# main.net
KiCad netlist of a schematic drawn in EAGLE
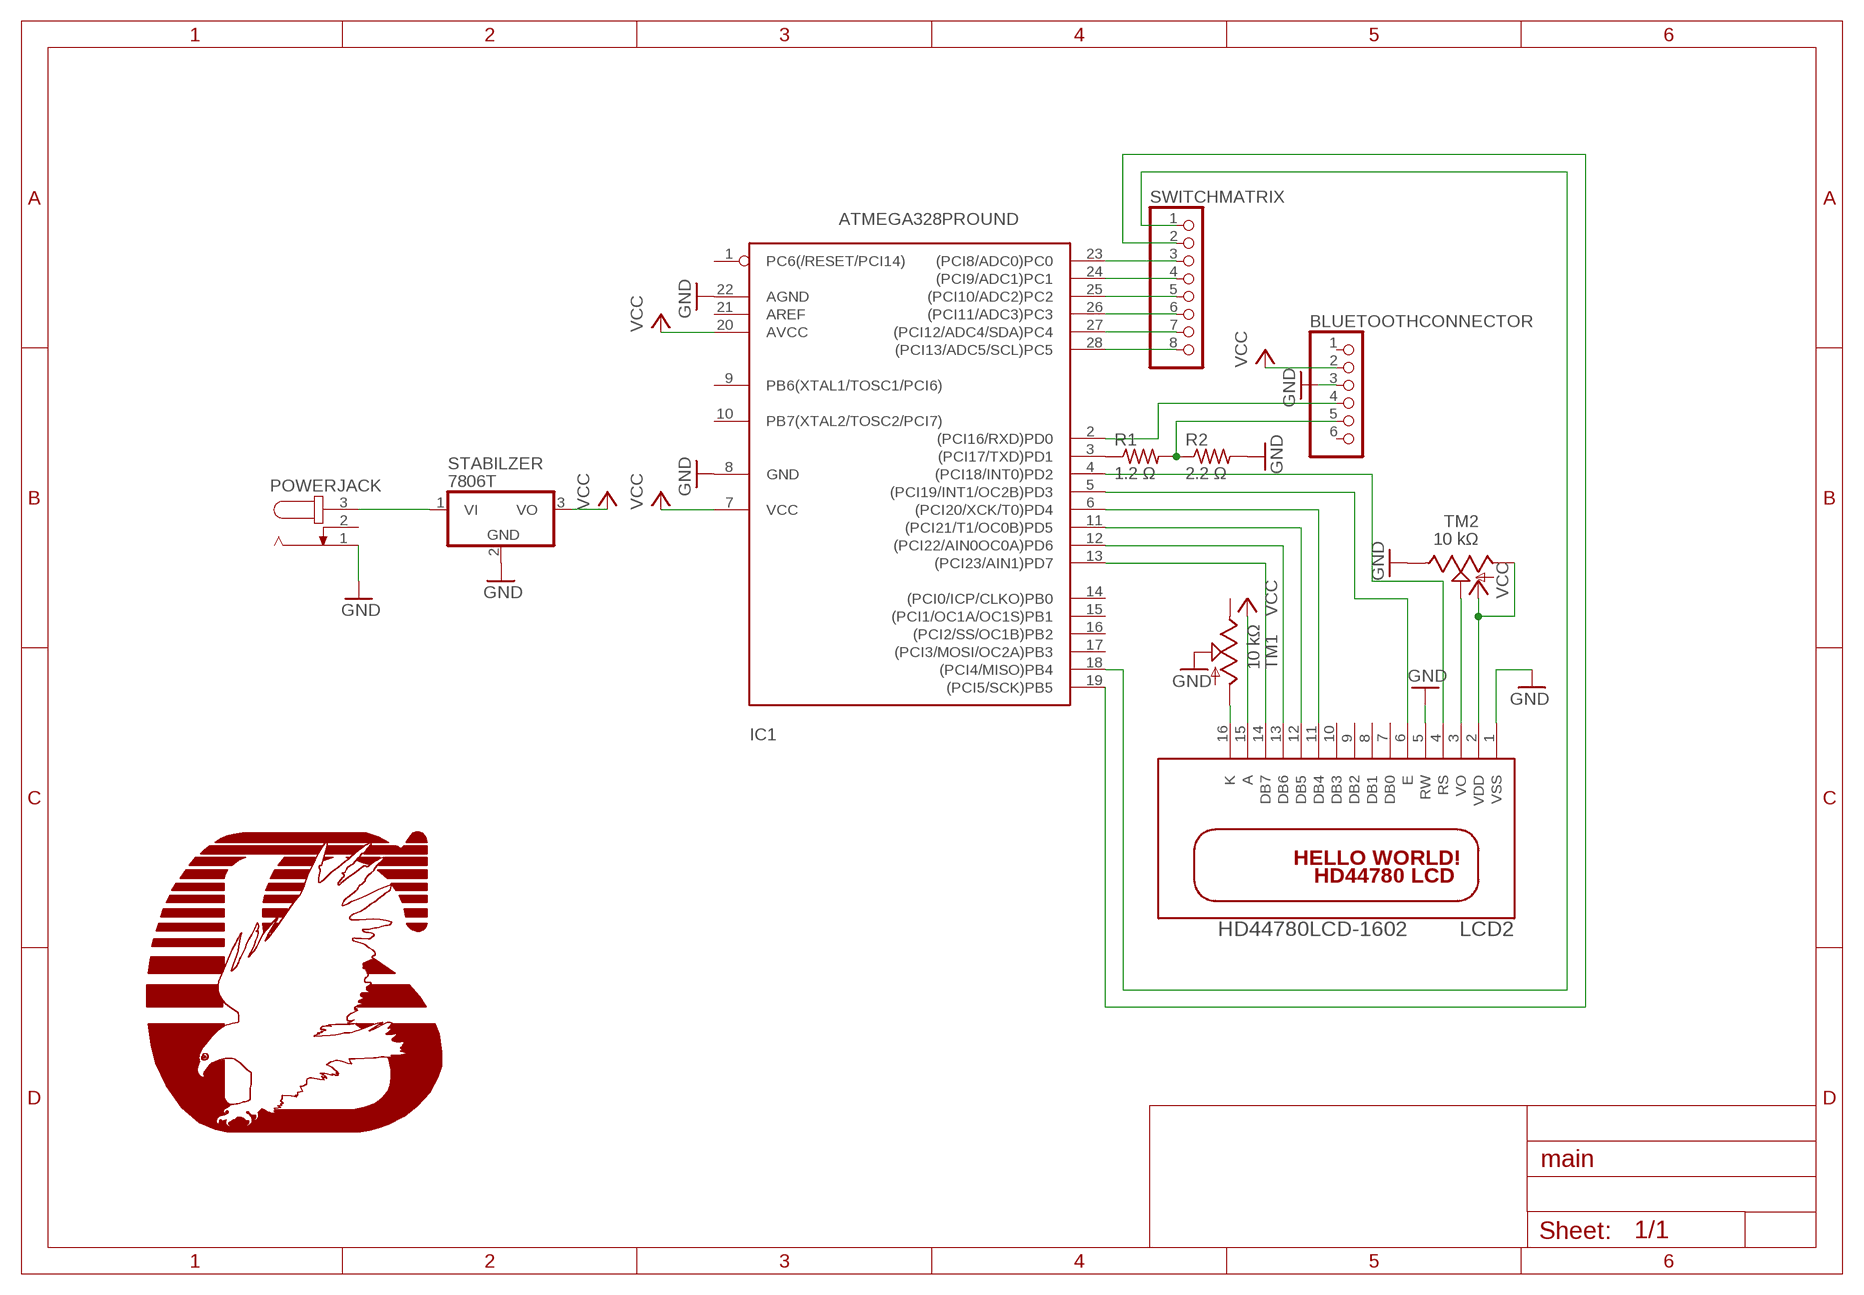
[diagram p0: schematic, sheet 1]

(export (version "E")
  (design (tool "Eeschema 10.0.6"))
  (components
    (comp (ref "BLUETOOTHCONNECTOR")
      (value "PINHD-1X6B")
      (footprint "eagle-import:1X06-BIG")
      (libsource (lib "eagle-import") (part "PINHD-1X6B"))
    )
    (comp (ref "IC1")
      (value "ATMEGA328PROUND")
      (footprint "eagle-import:DIL28-3-ROUND")
      (libsource (lib "eagle-import") (part "ATMEGA328PROUND"))
    )
    (comp (ref "LCD2")
      (value "HD44780LCD-1602")
      (footprint "eagle-import:LCD1602")
      (libsource (lib "eagle-import") (part "HD44780LCD-1602"))
    )
    (comp (ref "POWERJACK")
      (value "JACK-PLUG0")
      (footprint "eagle-import:SPC4077")
      (libsource (lib "eagle-import") (part "JACK-PLUG0"))
    )
    (comp (ref "R1")
      (value "1.2 Ω")
      (footprint "eagle-import:0207_10")
      (libsource (lib "eagle-import") (part "R-US_0207/10"))
    )
    (comp (ref "R2")
      (value "2.2 Ω")
      (footprint "eagle-import:0207_10")
      (libsource (lib "eagle-import") (part "R-US_0207/10"))
    )
    (comp (ref "STABILZER")
      (value "7806T")
      (footprint "eagle-import:TO220H")
      (libsource (lib "eagle-import") (part "78T06"))
    )
    (comp (ref "SWITCHMATRIX")
      (value "PINHD-1X8BIG")
      (footprint "eagle-import:1X08-BIG")
      (libsource (lib "eagle-import") (part "PINHD-1X8BIG"))
    )
    (comp (ref "TM1")
      (value "10 kΩ")
      (footprint "eagle-import:6MM")
      (libsource (lib "eagle-import") (part "TRIM"))
    )
    (comp (ref "TM2")
      (value "10 kΩ")
      (footprint "eagle-import:6MM")
      (libsource (lib "eagle-import") (part "TRIM"))
    )
  )
  (nets
    (net (code "1") (name "GND") (class "Default")
      (node (ref "BLUETOOTHCONNECTOR") (pin "3") (pinfunction "3_3") (pintype "passive"))
      (node (ref "IC1") (pin "22") (pinfunction "AGND_22") (pintype "bidirectional"))
      (node (ref "IC1") (pin "8") (pinfunction "GND_8") (pintype "bidirectional"))
      (node (ref "LCD2") (pin "1") (pinfunction "VSS_1") (pintype "power_in"))
      (node (ref "LCD2") (pin "5") (pinfunction "RW_5") (pintype "input"))
      (node (ref "POWERJACK") (pin "1") (pinfunction "1_1") (pintype "passive"))
      (node (ref "R2") (pin "2") (pinfunction "2_2") (pintype "passive"))
      (node (ref "STABILZER") (pin "2") (pinfunction "GND_2") (pintype "passive"))
      (node (ref "TM1") (pin "S") (pinfunction "S_S") (pintype "passive"))
      (node (ref "TM2") (pin "E") (pinfunction "E_E") (pintype "passive"))
    )
    (net (code "2") (name "Net-(BLUETOOTHCONNECTOR-Pad5)") (class "Default")
      (node (ref "BLUETOOTHCONNECTOR") (pin "5") (pinfunction "5_5") (pintype "passive"))
      (node (ref "R1") (pin "2") (pinfunction "2_2") (pintype "passive"))
      (node (ref "R2") (pin "1") (pinfunction "1_1") (pintype "passive"))
    )
    (net (code "3") (name "Net-(IC1-(PCI4{slash}MISO)PB4)") (class "Default")
      (node (ref "IC1") (pin "18") (pinfunction "(PCI4/MISO)PB4_18") (pintype "bidirectional"))
      (node (ref "SWITCHMATRIX") (pin "1") (pinfunction "1_1") (pintype "passive"))
    )
    (net (code "4") (name "Net-(IC1-(PCI5{slash}SCK)PB5)") (class "Default")
      (node (ref "IC1") (pin "19") (pinfunction "(PCI5/SCK)PB5_19") (pintype "bidirectional"))
      (node (ref "SWITCHMATRIX") (pin "2") (pinfunction "2_2") (pintype "passive"))
    )
    (net (code "5") (name "Net-(IC1-(PCI8{slash}ADC0)PC0)") (class "Default")
      (node (ref "IC1") (pin "23") (pinfunction "(PCI8/ADC0)PC0_23") (pintype "bidirectional"))
      (node (ref "SWITCHMATRIX") (pin "3") (pinfunction "3_3") (pintype "passive"))
    )
    (net (code "6") (name "Net-(IC1-(PCI9{slash}ADC1)PC1)") (class "Default")
      (node (ref "IC1") (pin "24") (pinfunction "(PCI9/ADC1)PC1_24") (pintype "bidirectional"))
      (node (ref "SWITCHMATRIX") (pin "4") (pinfunction "4_4") (pintype "passive"))
    )
    (net (code "7") (name "Net-(IC1-(PCI10{slash}ADC2)PC2)") (class "Default")
      (node (ref "IC1") (pin "25") (pinfunction "(PCI10/ADC2)PC2_25") (pintype "bidirectional"))
      (node (ref "SWITCHMATRIX") (pin "5") (pinfunction "5_5") (pintype "passive"))
    )
    (net (code "8") (name "Net-(IC1-(PCI11{slash}ADC3)PC3)") (class "Default")
      (node (ref "IC1") (pin "26") (pinfunction "(PCI11/ADC3)PC3_26") (pintype "bidirectional"))
      (node (ref "SWITCHMATRIX") (pin "6") (pinfunction "6_6") (pintype "passive"))
    )
    (net (code "9") (name "Net-(IC1-(PCI12{slash}ADC4{slash}SDA)PC4)") (class "Default")
      (node (ref "IC1") (pin "27") (pinfunction "(PCI12/ADC4/SDA)PC4_27") (pintype "bidirectional"))
      (node (ref "SWITCHMATRIX") (pin "7") (pinfunction "7_7") (pintype "passive"))
    )
    (net (code "10") (name "Net-(IC1-(PCI13{slash}ADC5{slash}SCL)PC5)") (class "Default")
      (node (ref "IC1") (pin "28") (pinfunction "(PCI13/ADC5/SCL)PC5_28") (pintype "bidirectional"))
      (node (ref "SWITCHMATRIX") (pin "8") (pinfunction "8_8") (pintype "passive"))
    )
    (net (code "11") (name "Net-(IC1-(PCI16{slash}RXD)PD0)") (class "Default")
      (node (ref "BLUETOOTHCONNECTOR") (pin "4") (pinfunction "4_4") (pintype "passive"))
      (node (ref "IC1") (pin "2") (pinfunction "(PCI16/RXD)PD0_2") (pintype "bidirectional"))
    )
    (net (code "12") (name "Net-(IC1-(PCI17{slash}TXD)PD1)") (class "Default")
      (node (ref "IC1") (pin "3") (pinfunction "(PCI17/TXD)PD1_3") (pintype "bidirectional"))
      (node (ref "R1") (pin "1") (pinfunction "1_1") (pintype "passive"))
    )
    (net (code "13") (name "Net-(IC1-(PCI18{slash}INT0)PD2)") (class "Default")
      (node (ref "IC1") (pin "4") (pinfunction "(PCI18/INT0)PD2_4") (pintype "bidirectional"))
      (node (ref "LCD2") (pin "4") (pinfunction "RS_4") (pintype "input"))
    )
    (net (code "14") (name "Net-(IC1-(PCI19{slash}INT1{slash}OC2B)PD3)") (class "Default")
      (node (ref "IC1") (pin "5") (pinfunction "(PCI19/INT1/OC2B)PD3_5") (pintype "bidirectional"))
      (node (ref "LCD2") (pin "6") (pinfunction "E_6") (pintype "input"))
    )
    (net (code "15") (name "Net-(IC1-(PCI20{slash}XCK{slash}T0)PD4)") (class "Default")
      (node (ref "IC1") (pin "6") (pinfunction "(PCI20/XCK/T0)PD4_6") (pintype "bidirectional"))
      (node (ref "LCD2") (pin "11") (pinfunction "DB4_11") (pintype "bidirectional"))
    )
    (net (code "16") (name "Net-(IC1-(PCI21{slash}T1{slash}OC0B)PD5)") (class "Default")
      (node (ref "IC1") (pin "11") (pinfunction "(PCI21/T1/OC0B)PD5_11") (pintype "bidirectional"))
      (node (ref "LCD2") (pin "12") (pinfunction "DB5_12") (pintype "bidirectional"))
    )
    (net (code "17") (name "Net-(IC1-(PCI22{slash}AIN0OC0A)PD6)") (class "Default")
      (node (ref "IC1") (pin "12") (pinfunction "(PCI22/AIN0OC0A)PD6_12") (pintype "bidirectional"))
      (node (ref "LCD2") (pin "13") (pinfunction "DB6_13") (pintype "bidirectional"))
    )
    (net (code "18") (name "Net-(IC1-(PCI23{slash}AIN1)PD7)") (class "Default")
      (node (ref "IC1") (pin "13") (pinfunction "(PCI23/AIN1)PD7_13") (pintype "bidirectional"))
      (node (ref "LCD2") (pin "14") (pinfunction "DB7_14") (pintype "bidirectional"))
    )
    (net (code "19") (name "Net-(LCD2-K)") (class "Default")
      (node (ref "LCD2") (pin "16") (pinfunction "K_16") (pintype "input"))
      (node (ref "TM1") (pin "A") (pinfunction "A_A") (pintype "passive"))
    )
    (net (code "20") (name "Net-(LCD2-VO)") (class "Default")
      (node (ref "LCD2") (pin "3") (pinfunction "VO_3") (pintype "input"))
      (node (ref "TM2") (pin "S") (pinfunction "S_S") (pintype "passive"))
    )
    (net (code "21") (name "Net-(STABILZER-VI)") (class "Default")
      (node (ref "POWERJACK") (pin "3") (pinfunction "3_3") (pintype "passive"))
      (node (ref "STABILZER") (pin "1") (pinfunction "VI_1") (pintype "input"))
    )
    (net (code "22") (name "VCC") (class "Default")
      (node (ref "BLUETOOTHCONNECTOR") (pin "2") (pinfunction "2_2") (pintype "passive"))
      (node (ref "IC1") (pin "20") (pinfunction "AVCC_20") (pintype "bidirectional"))
      (node (ref "IC1") (pin "7") (pinfunction "VCC_7") (pintype "bidirectional"))
      (node (ref "LCD2") (pin "15") (pinfunction "A_15") (pintype "input"))
      (node (ref "LCD2") (pin "2") (pinfunction "VDD_2") (pintype "power_in"))
      (node (ref "STABILZER") (pin "3") (pinfunction "VO_3") (pintype "passive"))
      (node (ref "TM2") (pin "A") (pinfunction "A_A") (pintype "passive"))
    )
    (net (code "23") (name "unconnected-(BLUETOOTHCONNECTOR-Pad1)") (class "Default")
      (node (ref "BLUETOOTHCONNECTOR") (pin "1") (pinfunction "1_1") (pintype "passive"))
    )
    (net (code "24") (name "unconnected-(BLUETOOTHCONNECTOR-Pad6)") (class "Default")
      (node (ref "BLUETOOTHCONNECTOR") (pin "6") (pinfunction "6_6") (pintype "passive"))
    )
    (net (code "25") (name "unconnected-(IC1-(PCI0{slash}ICP{slash}CLKO)PB0-Pad14)") (class "Default")
      (node (ref "IC1") (pin "14") (pinfunction "(PCI0/ICP/CLKO)PB0_14") (pintype "bidirectional"))
    )
    (net (code "26") (name "unconnected-(IC1-(PCI1{slash}OC1A{slash}OC1S)PB1-Pad15)") (class "Default")
      (node (ref "IC1") (pin "15") (pinfunction "(PCI1/OC1A/OC1S)PB1_15") (pintype "bidirectional"))
    )
    (net (code "27") (name "unconnected-(IC1-(PCI2{slash}SS{slash}OC1B)PB2-Pad16)") (class "Default")
      (node (ref "IC1") (pin "16") (pinfunction "(PCI2/SS/OC1B)PB2_16") (pintype "bidirectional"))
    )
    (net (code "28") (name "unconnected-(IC1-(PCI3{slash}MOSI{slash}OC2A)PB3-Pad17)") (class "Default")
      (node (ref "IC1") (pin "17") (pinfunction "(PCI3/MOSI/OC2A)PB3_17") (pintype "bidirectional"))
    )
    (net (code "29") (name "unconnected-(IC1-AREF-Pad21)") (class "Default")
      (node (ref "IC1") (pin "21") (pinfunction "AREF_21") (pintype "bidirectional"))
    )
    (net (code "30") (name "unconnected-(IC1-PB6(XTAL1{slash}TOSC1{slash}PCI6)-Pad9)") (class "Default")
      (node (ref "IC1") (pin "9") (pinfunction "PB6(XTAL1/TOSC1/PCI6)_9") (pintype "bidirectional"))
    )
    (net (code "31") (name "unconnected-(IC1-PB7(XTAL2{slash}TOSC2{slash}PCI7)-Pad10)") (class "Default")
      (node (ref "IC1") (pin "10") (pinfunction "PB7(XTAL2/TOSC2/PCI7)_10") (pintype "bidirectional"))
    )
    (net (code "32") (name "unconnected-(IC1-PC6({slash}RESET{slash}PCI14)-Pad1)") (class "Default")
      (node (ref "IC1") (pin "1") (pinfunction "PC6(/RESET/PCI14)_1") (pintype "bidirectional"))
    )
    (net (code "33") (name "unconnected-(LCD2-DB0-Pad7)") (class "Default")
      (node (ref "LCD2") (pin "7") (pinfunction "DB0_7") (pintype "bidirectional"))
    )
    (net (code "34") (name "unconnected-(LCD2-DB1-Pad8)") (class "Default")
      (node (ref "LCD2") (pin "8") (pinfunction "DB1_8") (pintype "bidirectional"))
    )
    (net (code "35") (name "unconnected-(LCD2-DB2-Pad9)") (class "Default")
      (node (ref "LCD2") (pin "9") (pinfunction "DB2_9") (pintype "bidirectional"))
    )
    (net (code "36") (name "unconnected-(LCD2-DB3-Pad10)") (class "Default")
      (node (ref "LCD2") (pin "10") (pinfunction "DB3_10") (pintype "bidirectional"))
    )
    (net (code "37") (name "unconnected-(POWERJACK-Pad2)") (class "Default")
      (node (ref "POWERJACK") (pin "2") (pinfunction "2_2") (pintype "passive"))
    )
    (net (code "38") (name "unconnected-(TM1-PadE)") (class "Default")
      (node (ref "TM1") (pin "E") (pinfunction "E_E") (pintype "passive"))
    )
  )
)
